# LED_280x10.net
KiCad netlist of a schematic drawn in Altium Designer
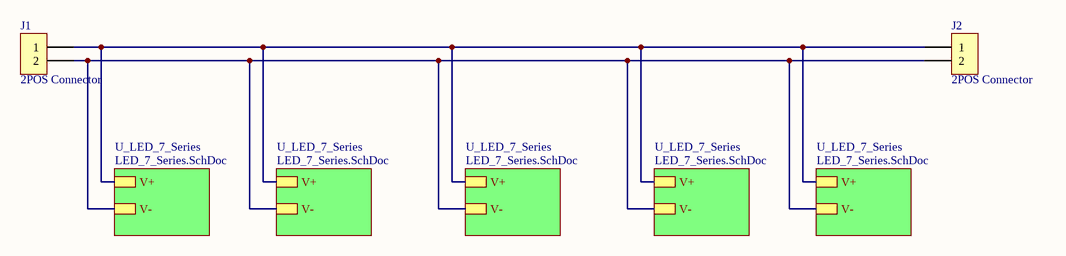
[diagram p0: LED_280x10.SchDoc]

(export (version "E")
  (design (tool "Eeschema 10.0.6"))
  (components
    (comp (ref "J1")
      (value "2POS Connector")
      (footprint "2 POS PADs")
      (libsource (lib "LED SchLib") (part "2POS Connector"))
    )
    (comp (ref "J2")
      (value "2POS Connector")
      (footprint "2 POS PADs")
      (libsource (lib "") (part "2POS Connector_1"))
    )
  )
  (nets
    (net (code "1") (name "/V+") (class "Default")
      (node (ref "J1") (pin "1") (pinfunction "1_1") (pintype "passive"))
      (node (ref "J2") (pin "1") (pinfunction "1_1") (pintype "passive"))
    )
    (net (code "2") (name "/V-") (class "Default")
      (node (ref "J1") (pin "2") (pinfunction "2_2") (pintype "passive"))
      (node (ref "J2") (pin "2") (pinfunction "2_2") (pintype "passive"))
    )
  )
)
